# NC1-1-TESTADAPTER-Top.net
KiCad netlist of a schematic drawn in Altium Designer
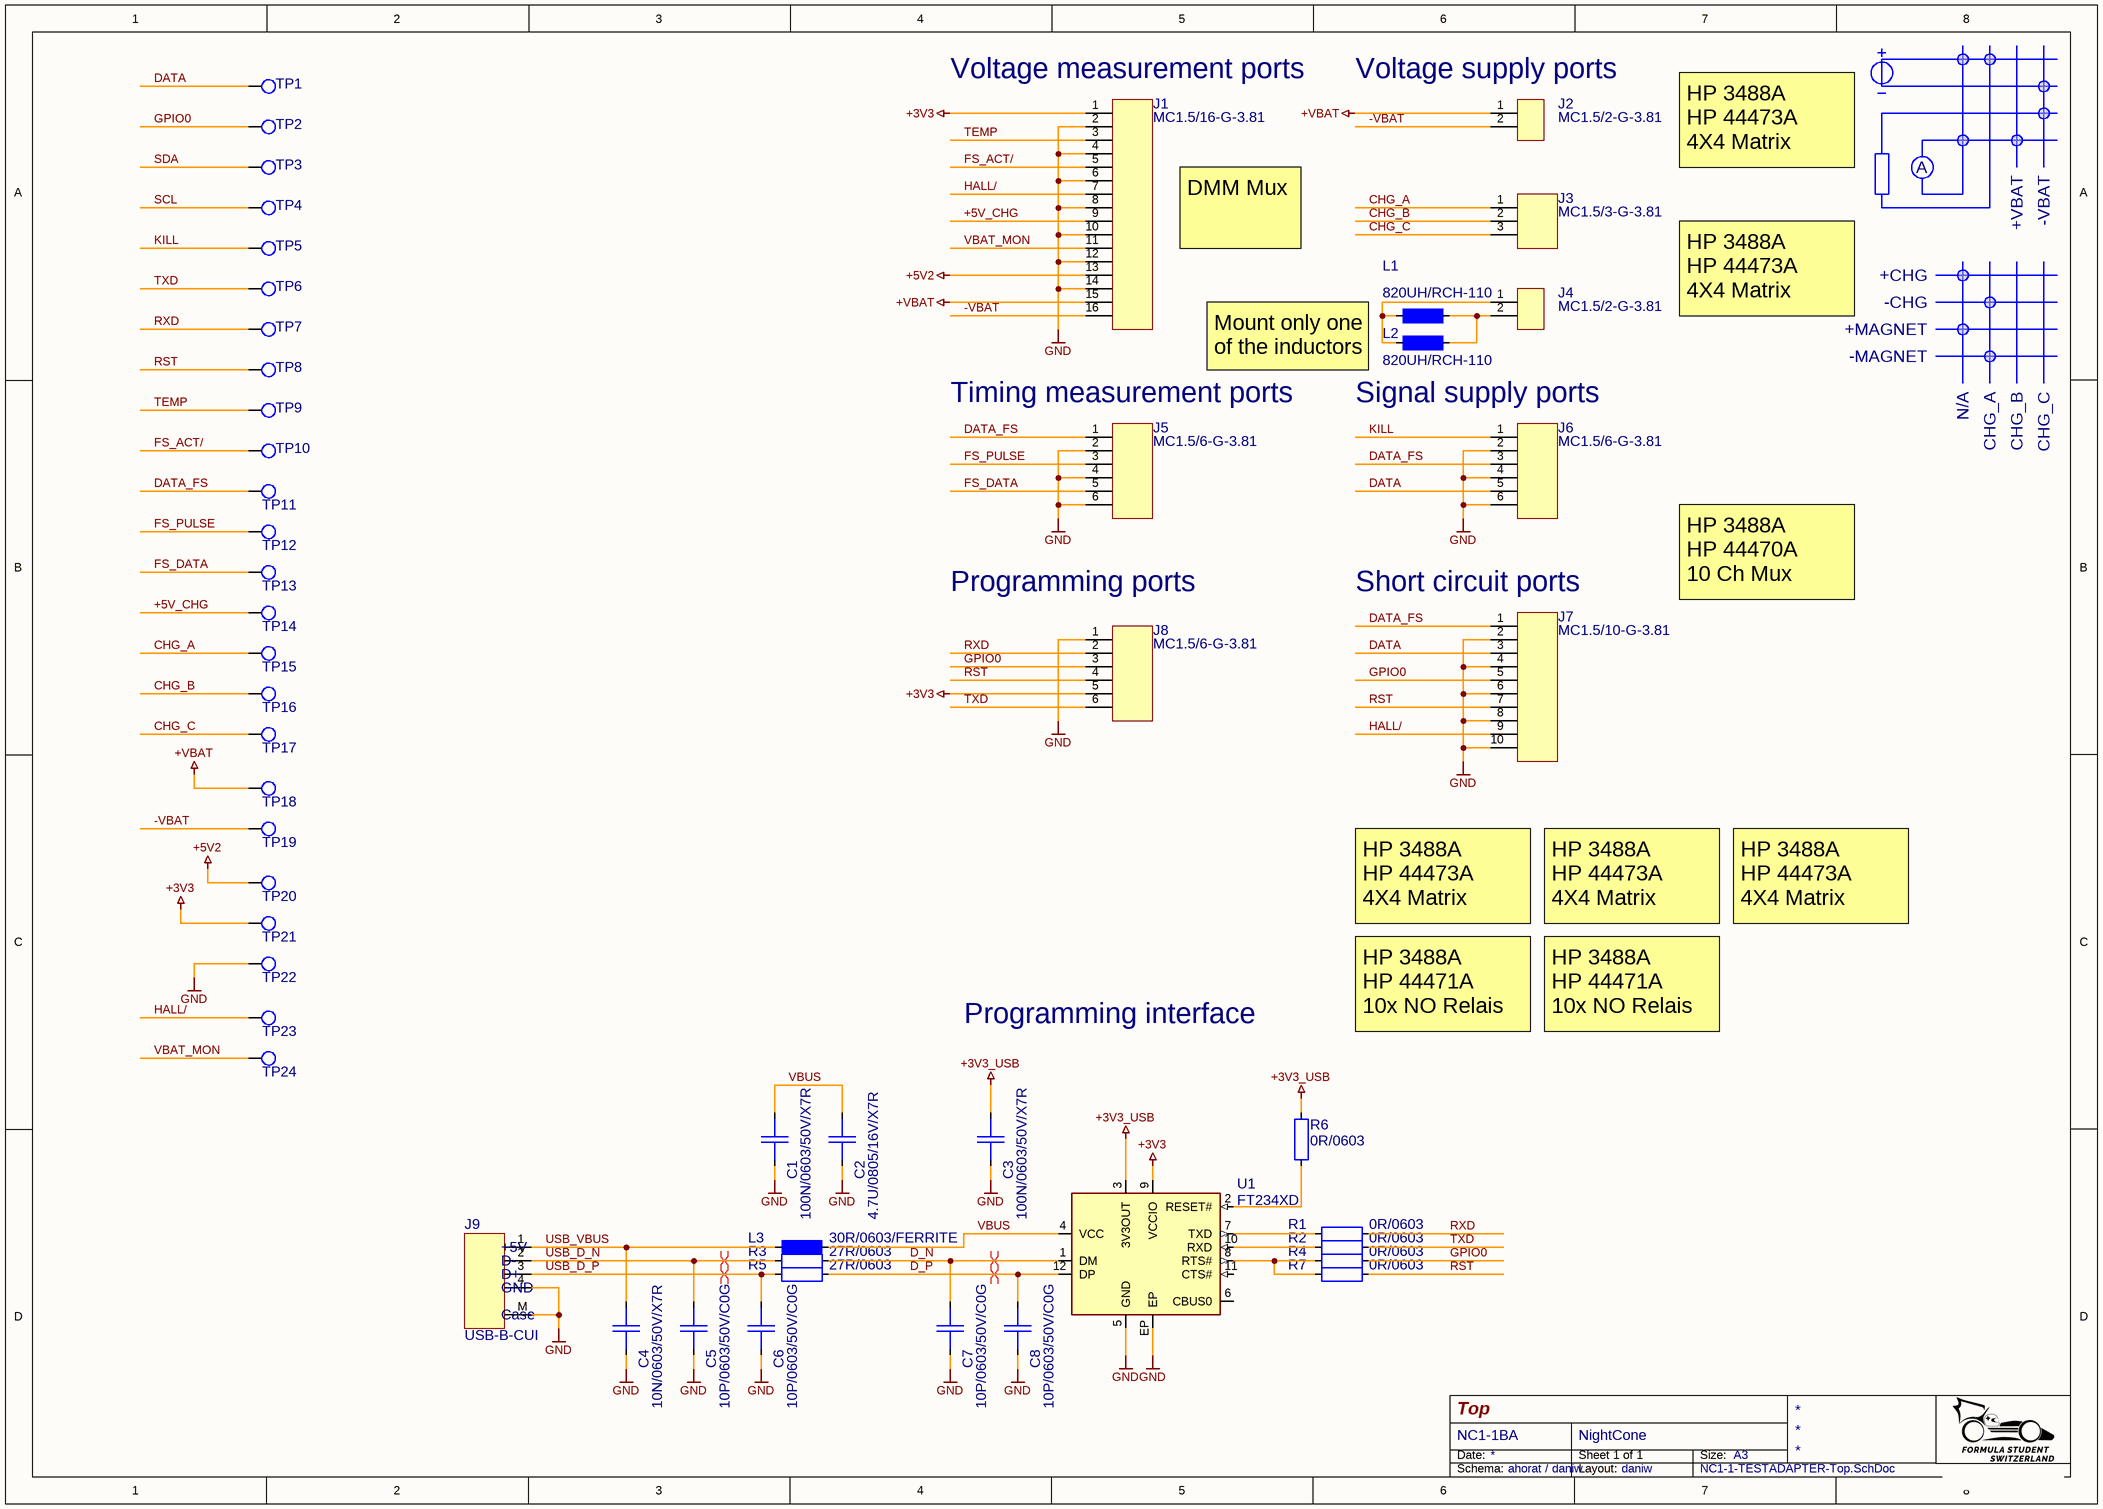
[diagram p0: NC1-1-TESTADAPTER-Top.SchDoc]

(export (version "E")
  (design (tool "Eeschema 10.0.6"))
  (components
    (comp (ref "C1")
      (value "100N/0603/50V/X7R")
      (footprint "CAP0603_X7R")
      (description "CAP SM 0603 100nF 50V X7R")
      (fields (field (name "MANUFACTURER") "GENERIC"))
      (libsource (lib "daniw_altium_lib") (part "C"))
    )
    (comp (ref "C2")
      (value "4.7U/0805/16V/X7R")
      (footprint "CAP0805_X7R")
      (description "CAP SM 0805 4.7uF 16V X7R")
      (fields (field (name "MANUFACTURER") "GENERIC"))
      (libsource (lib "daniw_altium_lib") (part "C"))
    )
    (comp (ref "C3")
      (value "100N/0603/50V/X7R")
      (footprint "CAP0603_X7R")
      (description "CAP SM 0603 100nF 50V X7R")
      (fields (field (name "MANUFACTURER") "GENERIC"))
      (libsource (lib "daniw_altium_lib") (part "C"))
    )
    (comp (ref "C4")
      (value "10N/0603/50V/X7R")
      (footprint "CAP0603_X7R")
      (description "CAP SM 0603 10nF 50V X7R")
      (fields (field (name "MANUFACTURER") "GENERIC"))
      (libsource (lib "daniw_altium_lib") (part "C"))
    )
    (comp (ref "C5")
      (value "10P/0603/50V/C0G")
      (footprint "CAP0603_C0G")
      (description "CAP SM 0603 10pF 50V C0G")
      (fields (field (name "MANUFACTURER") "GENERIC"))
      (libsource (lib "daniw_altium_lib") (part "C"))
    )
    (comp (ref "C6")
      (value "10P/0603/50V/C0G")
      (footprint "CAP0603_C0G")
      (description "CAP SM 0603 10pF 50V C0G")
      (fields (field (name "MANUFACTURER") "GENERIC"))
      (libsource (lib "daniw_altium_lib") (part "C"))
    )
    (comp (ref "C7")
      (value "10P/0603/50V/C0G")
      (footprint "CAP0603_C0G")
      (description "CAP SM 0603 10pF 50V C0G")
      (fields (field (name "MANUFACTURER") "GENERIC"))
      (libsource (lib "daniw_altium_lib") (part "C"))
    )
    (comp (ref "C8")
      (value "10P/0603/50V/C0G")
      (footprint "CAP0603_C0G")
      (description "CAP SM 0603 10pF 50V C0G")
      (fields (field (name "MANUFACTURER") "GENERIC"))
      (libsource (lib "daniw_altium_lib") (part "C"))
    )
    (comp (ref "J1")
      (value "MC1.5/16-G-3.81")
      (footprint "MC1.5/16-G-3.81")
      (description "Phoenix contact MC 1,5/ 16-G-3,81")
      (fields (field (name "MANUFACTURER") "Phoenix"))
      (libsource (lib "daniw_altium_lib") (part "CON16"))
    )
    (comp (ref "J2")
      (value "MC1.5/2-G-3.81")
      (footprint "MC1.5/2-G-3.81")
      (description "Phoenix contact MC 1,5/ 2-G-3,81")
      (fields (field (name "MANUFACTURER") "Phoenix"))
      (libsource (lib "daniw_altium_lib") (part "CON2"))
    )
    (comp (ref "J3")
      (value "MC1.5/3-G-3.81")
      (footprint "MC1.5/3-G-3.81")
      (description "Phoenix contact MC 1,5/ 3-G-3,81")
      (fields (field (name "MANUFACTURER") "Phoenix"))
      (libsource (lib "daniw_altium_lib") (part "CON3"))
    )
    (comp (ref "J4")
      (value "MC1.5/2-G-3.81")
      (footprint "MC1.5/2-G-3.81")
      (description "Phoenix contact MC 1,5/ 2-G-3,81")
      (fields (field (name "MANUFACTURER") "Phoenix"))
      (libsource (lib "daniw_altium_lib") (part "CON2"))
    )
    (comp (ref "J5")
      (value "MC1.5/6-G-3.81")
      (footprint "MC1.5/6-G-3.81")
      (description "Phoenix contact MC 1,5/ 6-G-3,81")
      (fields (field (name "MANUFACTURER") "Phoenix"))
      (libsource (lib "daniw_altium_lib") (part "CON6"))
    )
    (comp (ref "J6")
      (value "MC1.5/6-G-3.81")
      (footprint "MC1.5/6-G-3.81")
      (description "Phoenix contact MC 1,5/ 6-G-3,81")
      (fields (field (name "MANUFACTURER") "Phoenix"))
      (libsource (lib "daniw_altium_lib") (part "CON6"))
    )
    (comp (ref "J7")
      (value "MC1.5/10-G-3.81")
      (footprint "MC1.5/10-G-3.81")
      (description "Phoenix contact MC 1,5/ 10-G-3,81")
      (fields (field (name "MANUFACTURER") "Phoenix"))
      (libsource (lib "daniw_altium_lib") (part "CON10"))
    )
    (comp (ref "J8")
      (value "MC1.5/6-G-3.81")
      (footprint "MC1.5/6-G-3.81")
      (description "Phoenix contact MC 1,5/ 6-G-3,81")
      (fields (field (name "MANUFACTURER") "Phoenix"))
      (libsource (lib "daniw_altium_lib") (part "CON6"))
    )
    (comp (ref "J9")
      (value "USB-B-CUI")
      (footprint "USB-B_CUI_UJ2-BH-TH")
      (description "USB-B CUI UJ2-BH-TH")
      (fields (field (name "MANUFACTURER") "CUI"))
      (libsource (lib "daniw_altium_lib") (part "CON4-M_USB"))
    )
    (comp (ref "L1")
      (value "820UH/RCH-110")
      (footprint "RCH-110-SINGLE")
      (description "820UH unshielded inductor THT RCH-110")
      (fields (field (name "MANUFACTURER") "Sumida"))
      (libsource (lib "daniw_altium_lib") (part "L"))
    )
    (comp (ref "L2")
      (value "820UH/RCH-110")
      (footprint "RCH-110-SINGLE")
      (description "820UH unshielded inductor THT RCH-110")
      (fields (field (name "MANUFACTURER") "Sumida"))
      (libsource (lib "daniw_altium_lib") (part "L"))
    )
    (comp (ref "L3")
      (value "30R/0603/FERRITE")
      (footprint "FB0603")
      (description "30R@100MHz 5A 0603 Ferrite")
      (fields (field (name "MANUFACTURER") "GENERIC"))
      (libsource (lib "daniw_altium_lib") (part "Ferrite"))
    )
    (comp (ref "R1")
      (value "0R/0603")
      (footprint "R0603-0.40-WW")
      (description "RES SM 0603 0R")
      (fields (field (name "MANUFACTURER") "GENERIC"))
      (libsource (lib "daniw_altium_lib") (part "R"))
    )
    (comp (ref "R2")
      (value "0R/0603")
      (footprint "R0603-0.40-WW")
      (description "RES SM 0603 0R")
      (fields (field (name "MANUFACTURER") "GENERIC"))
      (libsource (lib "daniw_altium_lib") (part "R"))
    )
    (comp (ref "R3")
      (value "27R/0603")
      (footprint "R0603-0.40-WW")
      (description "RES SM 0603 27R")
      (fields (field (name "MANUFACTURER") "GENERIC"))
      (libsource (lib "daniw_altium_lib") (part "R"))
    )
    (comp (ref "R4")
      (value "0R/0603")
      (footprint "R0603-0.40-WW")
      (description "RES SM 0603 0R")
      (fields (field (name "MANUFACTURER") "GENERIC"))
      (libsource (lib "daniw_altium_lib") (part "R"))
    )
    (comp (ref "R5")
      (value "27R/0603")
      (footprint "R0603-0.40-WW")
      (description "RES SM 0603 27R")
      (fields (field (name "MANUFACTURER") "GENERIC"))
      (libsource (lib "daniw_altium_lib") (part "R"))
    )
    (comp (ref "R6")
      (value "0R/0603")
      (footprint "R0603-0.40-WW")
      (description "RES SM 0603 0R")
      (fields (field (name "MANUFACTURER") "GENERIC"))
      (libsource (lib "daniw_altium_lib") (part "R"))
    )
    (comp (ref "R7")
      (value "0R/0603")
      (footprint "R0603-0.40-WW")
      (description "RES SM 0603 0R")
      (fields (field (name "MANUFACTURER") "GENERIC"))
      (libsource (lib "daniw_altium_lib") (part "R"))
    )
    (comp (ref "TP1")
      (value "SPRING-PROBE-SLEEVE-25")
      (footprint "TP_SPRING_PROBE_S25-512")
      (fields (field (name "MANUFACTURER") "Harwin"))
      (libsource (lib "daniw_altium_lib") (part "Testpoint"))
    )
    (comp (ref "TP2")
      (value "SPRING-PROBE-SLEEVE-25")
      (footprint "TP_SPRING_PROBE_S25-512")
      (fields (field (name "MANUFACTURER") "Harwin"))
      (libsource (lib "daniw_altium_lib") (part "Testpoint"))
    )
    (comp (ref "TP3")
      (value "SPRING-PROBE-SLEEVE-25")
      (footprint "TP_SPRING_PROBE_S25-512")
      (fields (field (name "MANUFACTURER") "Harwin"))
      (libsource (lib "daniw_altium_lib") (part "Testpoint"))
    )
    (comp (ref "TP4")
      (value "SPRING-PROBE-SLEEVE-25")
      (footprint "TP_SPRING_PROBE_S25-512")
      (fields (field (name "MANUFACTURER") "Harwin"))
      (libsource (lib "daniw_altium_lib") (part "Testpoint"))
    )
    (comp (ref "TP5")
      (value "SPRING-PROBE-SLEEVE-25")
      (footprint "TP_SPRING_PROBE_S25-512")
      (fields (field (name "MANUFACTURER") "Harwin"))
      (libsource (lib "daniw_altium_lib") (part "Testpoint"))
    )
    (comp (ref "TP6")
      (value "SPRING-PROBE-SLEEVE-25")
      (footprint "TP_SPRING_PROBE_S25-512")
      (fields (field (name "MANUFACTURER") "Harwin"))
      (libsource (lib "daniw_altium_lib") (part "Testpoint"))
    )
    (comp (ref "TP7")
      (value "SPRING-PROBE-SLEEVE-25")
      (footprint "TP_SPRING_PROBE_S25-512")
      (fields (field (name "MANUFACTURER") "Harwin"))
      (libsource (lib "daniw_altium_lib") (part "Testpoint"))
    )
    (comp (ref "TP8")
      (value "SPRING-PROBE-SLEEVE-25")
      (footprint "TP_SPRING_PROBE_S25-512")
      (fields (field (name "MANUFACTURER") "Harwin"))
      (libsource (lib "daniw_altium_lib") (part "Testpoint"))
    )
    (comp (ref "TP9")
      (value "SPRING-PROBE-SLEEVE-25")
      (footprint "TP_SPRING_PROBE_S25-512")
      (fields (field (name "MANUFACTURER") "Harwin"))
      (libsource (lib "daniw_altium_lib") (part "Testpoint"))
    )
    (comp (ref "TP10")
      (value "SPRING-PROBE-SLEEVE-25")
      (footprint "TP_SPRING_PROBE_S25-512")
      (fields (field (name "MANUFACTURER") "Harwin"))
      (libsource (lib "daniw_altium_lib") (part "Testpoint"))
    )
    (comp (ref "TP11")
      (value "SPRING-PROBE-SLEEVE-25")
      (footprint "TP_SPRING_PROBE_S25-512")
      (fields (field (name "MANUFACTURER") "Harwin"))
      (libsource (lib "daniw_altium_lib") (part "Testpoint"))
    )
    (comp (ref "TP12")
      (value "SPRING-PROBE-SLEEVE-25")
      (footprint "TP_SPRING_PROBE_S25-512")
      (fields (field (name "MANUFACTURER") "Harwin"))
      (libsource (lib "daniw_altium_lib") (part "Testpoint"))
    )
    (comp (ref "TP13")
      (value "SPRING-PROBE-SLEEVE-25")
      (footprint "TP_SPRING_PROBE_S25-512")
      (fields (field (name "MANUFACTURER") "Harwin"))
      (libsource (lib "daniw_altium_lib") (part "Testpoint"))
    )
    (comp (ref "TP14")
      (value "SPRING-PROBE-SLEEVE-25")
      (footprint "TP_SPRING_PROBE_S25-512")
      (fields (field (name "MANUFACTURER") "Harwin"))
      (libsource (lib "daniw_altium_lib") (part "Testpoint"))
    )
    (comp (ref "TP15")
      (value "SPRING-PROBE-SLEEVE-25")
      (footprint "TP_SPRING_PROBE_S25-512")
      (fields (field (name "MANUFACTURER") "Harwin"))
      (libsource (lib "daniw_altium_lib") (part "Testpoint"))
    )
    (comp (ref "TP16")
      (value "SPRING-PROBE-SLEEVE-25")
      (footprint "TP_SPRING_PROBE_S25-512")
      (fields (field (name "MANUFACTURER") "Harwin"))
      (libsource (lib "daniw_altium_lib") (part "Testpoint"))
    )
    (comp (ref "TP17")
      (value "SPRING-PROBE-SLEEVE-25")
      (footprint "TP_SPRING_PROBE_S25-512")
      (fields (field (name "MANUFACTURER") "Harwin"))
      (libsource (lib "daniw_altium_lib") (part "Testpoint"))
    )
    (comp (ref "TP18")
      (value "SPRING-PROBE-SLEEVE-25")
      (footprint "TP_SPRING_PROBE_S25-512")
      (fields (field (name "MANUFACTURER") "Harwin"))
      (libsource (lib "daniw_altium_lib") (part "Testpoint"))
    )
    (comp (ref "TP19")
      (value "SPRING-PROBE-SLEEVE-25")
      (footprint "TP_SPRING_PROBE_S25-512")
      (fields (field (name "MANUFACTURER") "Harwin"))
      (libsource (lib "daniw_altium_lib") (part "Testpoint"))
    )
    (comp (ref "TP20")
      (value "SPRING-PROBE-SLEEVE-25")
      (footprint "TP_SPRING_PROBE_S25-512")
      (fields (field (name "MANUFACTURER") "Harwin"))
      (libsource (lib "daniw_altium_lib") (part "Testpoint"))
    )
    (comp (ref "TP21")
      (value "SPRING-PROBE-SLEEVE-25")
      (footprint "TP_SPRING_PROBE_S25-512")
      (fields (field (name "MANUFACTURER") "Harwin"))
      (libsource (lib "daniw_altium_lib") (part "Testpoint"))
    )
    (comp (ref "TP22")
      (value "SPRING-PROBE-SLEEVE-25")
      (footprint "TP_SPRING_PROBE_S25-512")
      (fields (field (name "MANUFACTURER") "Harwin"))
      (libsource (lib "daniw_altium_lib") (part "Testpoint"))
    )
    (comp (ref "TP23")
      (value "SPRING-PROBE-SLEEVE-25")
      (footprint "TP_SPRING_PROBE_S25-512")
      (fields (field (name "MANUFACTURER") "Harwin"))
      (libsource (lib "daniw_altium_lib") (part "Testpoint"))
    )
    (comp (ref "TP24")
      (value "SPRING-PROBE-SLEEVE-25")
      (footprint "TP_SPRING_PROBE_S25-512")
      (fields (field (name "MANUFACTURER") "Harwin"))
      (libsource (lib "daniw_altium_lib") (part "Testpoint"))
    )
    (comp (ref "U1")
      (value "FT234XD")
      (footprint "DFN045P300X300X080-12-EP160X250")
      (description "FT234XD USB TO BASIC UART IC")
      (fields (field (name "MANUFACTURER") "FTDI"))
      (libsource (lib "daniw_altium_lib") (part "FT234XD"))
    )
  )
  (nets
    (net (code "1") (name "+3V3") (class "Default")
      (node (ref "J1") (pin "1") (pintype "passive"))
      (node (ref "J8") (pin "5") (pintype "passive"))
      (node (ref "TP21") (pin "1") (pinfunction "1_1") (pintype "passive"))
      (node (ref "U1") (pin "9") (pinfunction "VCCIO_9") (pintype "passive"))
    )
    (net (code "2") (name "+3V3_USB") (class "Default")
      (node (ref "C3") (pin "1") (pinfunction "1_1") (pintype "passive"))
      (node (ref "R6") (pin "1") (pinfunction "1_1") (pintype "passive"))
      (node (ref "U1") (pin "3") (pinfunction "3V3OUT_3") (pintype "passive"))
    )
    (net (code "3") (name "+5V2") (class "Default")
      (node (ref "J1") (pin "13") (pintype "passive"))
      (node (ref "TP20") (pin "1") (pinfunction "1_1") (pintype "passive"))
    )
    (net (code "4") (name "+VBAT") (class "Default")
      (node (ref "J1") (pin "15") (pintype "passive"))
      (node (ref "J2") (pin "1") (pintype "passive"))
      (node (ref "TP18") (pin "1") (pinfunction "1_1") (pintype "passive"))
    )
    (net (code "5") (name "/+5V_CHG") (class "Default")
      (node (ref "J1") (pin "9") (pintype "passive"))
      (node (ref "TP14") (pin "1") (pinfunction "1_1") (pintype "passive"))
    )
    (net (code "6") (name "/-VBAT") (class "Default")
      (node (ref "J1") (pin "16") (pintype "passive"))
      (node (ref "J2") (pin "2") (pintype "passive"))
      (node (ref "TP19") (pin "1") (pinfunction "1_1") (pintype "passive"))
    )
    (net (code "7") (name "/CHG_A") (class "Default")
      (node (ref "J3") (pin "1") (pintype "passive"))
      (node (ref "TP15") (pin "1") (pinfunction "1_1") (pintype "passive"))
    )
    (net (code "8") (name "/CHG_B") (class "Default")
      (node (ref "J3") (pin "2") (pintype "passive"))
      (node (ref "TP16") (pin "1") (pinfunction "1_1") (pintype "passive"))
    )
    (net (code "9") (name "/CHG_C") (class "Default")
      (node (ref "J3") (pin "3") (pintype "passive"))
      (node (ref "TP17") (pin "1") (pinfunction "1_1") (pintype "passive"))
    )
    (net (code "10") (name "/DATA") (class "Default")
      (node (ref "J6") (pin "5") (pintype "passive"))
      (node (ref "J7") (pin "3") (pintype "passive"))
      (node (ref "TP1") (pin "1") (pinfunction "1_1") (pintype "passive"))
    )
    (net (code "11") (name "/DATA_FS") (class "Default")
      (node (ref "J5") (pin "1") (pintype "passive"))
      (node (ref "J6") (pin "3") (pintype "passive"))
      (node (ref "J7") (pin "1") (pintype "passive"))
      (node (ref "TP11") (pin "1") (pinfunction "1_1") (pintype "passive"))
    )
    (net (code "12") (name "/D_N") (class "Default")
      (node (ref "C7") (pin "1") (pinfunction "1_1") (pintype "passive"))
      (node (ref "R3") (pin "2") (pinfunction "2_2") (pintype "passive"))
      (node (ref "U1") (pin "1") (pinfunction "DM_1") (pintype "bidirectional"))
    )
    (net (code "13") (name "/D_P") (class "Default")
      (node (ref "C8") (pin "1") (pinfunction "1_1") (pintype "passive"))
      (node (ref "R5") (pin "2") (pinfunction "2_2") (pintype "passive"))
      (node (ref "U1") (pin "12") (pinfunction "DP_12") (pintype "bidirectional"))
    )
    (net (code "14") (name "/FS_ACT{slash}") (class "Default")
      (node (ref "J1") (pin "5") (pintype "passive"))
      (node (ref "TP10") (pin "1") (pinfunction "1_1") (pintype "passive"))
    )
    (net (code "15") (name "/FS_DATA") (class "Default")
      (node (ref "J5") (pin "5") (pintype "passive"))
      (node (ref "TP13") (pin "1") (pinfunction "1_1") (pintype "passive"))
    )
    (net (code "16") (name "/FS_PULSE") (class "Default")
      (node (ref "J5") (pin "3") (pintype "passive"))
      (node (ref "TP12") (pin "1") (pinfunction "1_1") (pintype "passive"))
    )
    (net (code "17") (name "/GPIO0") (class "Default")
      (node (ref "J7") (pin "5") (pintype "passive"))
      (node (ref "J8") (pin "3") (pintype "passive"))
      (node (ref "R4") (pin "2") (pinfunction "2_2") (pintype "passive"))
      (node (ref "TP2") (pin "1") (pinfunction "1_1") (pintype "passive"))
    )
    (net (code "18") (name "/HALL{slash}") (class "Default")
      (node (ref "J1") (pin "7") (pintype "passive"))
      (node (ref "J7") (pin "9") (pintype "passive"))
      (node (ref "TP23") (pin "1") (pinfunction "1_1") (pintype "passive"))
    )
    (net (code "19") (name "/KILL") (class "Default")
      (node (ref "J6") (pin "1") (pintype "passive"))
      (node (ref "TP5") (pin "1") (pinfunction "1_1") (pintype "passive"))
    )
    (net (code "20") (name "/RST") (class "Default")
      (node (ref "J7") (pin "7") (pintype "passive"))
      (node (ref "J8") (pin "4") (pintype "passive"))
      (node (ref "R7") (pin "2") (pinfunction "2_2") (pintype "passive"))
      (node (ref "TP8") (pin "1") (pinfunction "1_1") (pintype "passive"))
    )
    (net (code "21") (name "/RXD") (class "Default")
      (node (ref "J8") (pin "2") (pintype "passive"))
      (node (ref "R1") (pin "2") (pinfunction "2_2") (pintype "passive"))
      (node (ref "TP7") (pin "1") (pinfunction "1_1") (pintype "passive"))
    )
    (net (code "22") (name "/SCL") (class "Default")
      (node (ref "TP4") (pin "1") (pinfunction "1_1") (pintype "passive"))
    )
    (net (code "23") (name "/SDA") (class "Default")
      (node (ref "TP3") (pin "1") (pinfunction "1_1") (pintype "passive"))
    )
    (net (code "24") (name "/TEMP") (class "Default")
      (node (ref "J1") (pin "3") (pintype "passive"))
      (node (ref "TP9") (pin "1") (pinfunction "1_1") (pintype "passive"))
    )
    (net (code "25") (name "/TXD") (class "Default")
      (node (ref "J8") (pin "6") (pintype "passive"))
      (node (ref "R2") (pin "2") (pinfunction "2_2") (pintype "passive"))
      (node (ref "TP6") (pin "1") (pinfunction "1_1") (pintype "passive"))
    )
    (net (code "26") (name "/USB_D_N") (class "Default")
      (node (ref "C5") (pin "1") (pinfunction "1_1") (pintype "passive"))
      (node (ref "J9") (pin "2") (pintype "passive"))
      (node (ref "R3") (pin "1") (pinfunction "1_1") (pintype "passive"))
    )
    (net (code "27") (name "/USB_D_P") (class "Default")
      (node (ref "C6") (pin "1") (pinfunction "1_1") (pintype "passive"))
      (node (ref "J9") (pin "3") (pintype "passive"))
      (node (ref "R5") (pin "1") (pinfunction "1_1") (pintype "passive"))
    )
    (net (code "28") (name "/USB_VBUS") (class "Default")
      (node (ref "C4") (pin "1") (pinfunction "1_1") (pintype "passive"))
      (node (ref "J9") (pin "1") (pintype "passive"))
      (node (ref "L3") (pin "1") (pinfunction "1_1") (pintype "passive"))
    )
    (net (code "29") (name "/VBAT_MON") (class "Default")
      (node (ref "J1") (pin "11") (pintype "passive"))
      (node (ref "TP24") (pin "1") (pinfunction "1_1") (pintype "passive"))
    )
    (net (code "30") (name "/VBUS") (class "Default")
      (node (ref "C1") (pin "1") (pinfunction "1_1") (pintype "passive"))
      (node (ref "C2") (pin "1") (pinfunction "1_1") (pintype "passive"))
      (node (ref "L3") (pin "2") (pinfunction "2_2") (pintype "passive"))
      (node (ref "U1") (pin "4") (pinfunction "VCC_4") (pintype "passive"))
    )
    (net (code "31") (name "GND") (class "Default")
      (node (ref "C1") (pin "2") (pinfunction "2_2") (pintype "passive"))
      (node (ref "C2") (pin "2") (pinfunction "2_2") (pintype "passive"))
      (node (ref "C3") (pin "2") (pinfunction "2_2") (pintype "passive"))
      (node (ref "C4") (pin "2") (pinfunction "2_2") (pintype "passive"))
      (node (ref "C5") (pin "2") (pinfunction "2_2") (pintype "passive"))
      (node (ref "C6") (pin "2") (pinfunction "2_2") (pintype "passive"))
      (node (ref "C7") (pin "2") (pinfunction "2_2") (pintype "passive"))
      (node (ref "C8") (pin "2") (pinfunction "2_2") (pintype "passive"))
      (node (ref "J1") (pin "10") (pintype "passive"))
      (node (ref "J1") (pin "12") (pintype "passive"))
      (node (ref "J1") (pin "14") (pintype "passive"))
      (node (ref "J1") (pin "2") (pintype "passive"))
      (node (ref "J1") (pin "4") (pintype "passive"))
      (node (ref "J1") (pin "6") (pintype "passive"))
      (node (ref "J1") (pin "8") (pintype "passive"))
      (node (ref "J5") (pin "2") (pintype "passive"))
      (node (ref "J5") (pin "4") (pintype "passive"))
      (node (ref "J5") (pin "6") (pintype "passive"))
      (node (ref "J6") (pin "2") (pintype "passive"))
      (node (ref "J6") (pin "4") (pintype "passive"))
      (node (ref "J6") (pin "6") (pintype "passive"))
      (node (ref "J7") (pin "10") (pintype "passive"))
      (node (ref "J7") (pin "2") (pintype "passive"))
      (node (ref "J7") (pin "4") (pintype "passive"))
      (node (ref "J7") (pin "6") (pintype "passive"))
      (node (ref "J7") (pin "8") (pintype "passive"))
      (node (ref "J8") (pin "1") (pintype "passive"))
      (node (ref "J9") (pin "4") (pintype "passive"))
      (node (ref "J9") (pin "M") (pintype "passive"))
      (node (ref "TP22") (pin "1") (pinfunction "1_1") (pintype "passive"))
      (node (ref "U1") (pin "5") (pinfunction "GND_5") (pintype "passive"))
      (node (ref "U1") (pin "EP") (pinfunction "EP_EP") (pintype "passive"))
    )
    (net (code "32") (name "Net-(J4-Pad1)") (class "Default")
      (node (ref "J4") (pin "1") (pintype "passive"))
      (node (ref "L1") (pin "1") (pinfunction "1_1") (pintype "passive"))
      (node (ref "L2") (pin "1") (pinfunction "1_1") (pintype "passive"))
    )
    (net (code "33") (name "Net-(J4-Pad2)") (class "Default")
      (node (ref "J4") (pin "2") (pintype "passive"))
      (node (ref "L1") (pin "2") (pinfunction "2_2") (pintype "passive"))
      (node (ref "L2") (pin "2") (pinfunction "2_2") (pintype "passive"))
    )
    (net (code "34") (name "Net-(U1-RESET#)") (class "Default")
      (node (ref "R6") (pin "2") (pinfunction "2_2") (pintype "passive"))
      (node (ref "U1") (pin "2") (pinfunction "RESET#_2") (pintype "input"))
    )
    (net (code "35") (name "Net-(U1-RTS#)") (class "Default")
      (node (ref "R4") (pin "1") (pinfunction "1_1") (pintype "passive"))
      (node (ref "R7") (pin "1") (pinfunction "1_1") (pintype "passive"))
      (node (ref "U1") (pin "8") (pinfunction "RTS#_8") (pintype "output"))
    )
    (net (code "36") (name "Net-(U1-RXD)") (class "Default")
      (node (ref "R2") (pin "1") (pinfunction "1_1") (pintype "passive"))
      (node (ref "U1") (pin "10") (pinfunction "RXD_10") (pintype "input"))
    )
    (net (code "37") (name "Net-(U1-TXD)") (class "Default")
      (node (ref "R1") (pin "1") (pinfunction "1_1") (pintype "passive"))
      (node (ref "U1") (pin "7") (pinfunction "TXD_7") (pintype "output"))
    )
    (net (code "38") (name "unconnected-(U1-CBUS0-Pad6)") (class "Default")
      (node (ref "U1") (pin "6") (pinfunction "CBUS0_6") (pintype "bidirectional"))
    )
    (net (code "39") (name "unconnected-(U1-CTS#-Pad11)") (class "Default")
      (node (ref "U1") (pin "11") (pinfunction "CTS#_11") (pintype "input"))
    )
  )
)
